# SCH-2-Main_Controls.net
KiCad netlist of a schematic drawn in Altium Designer
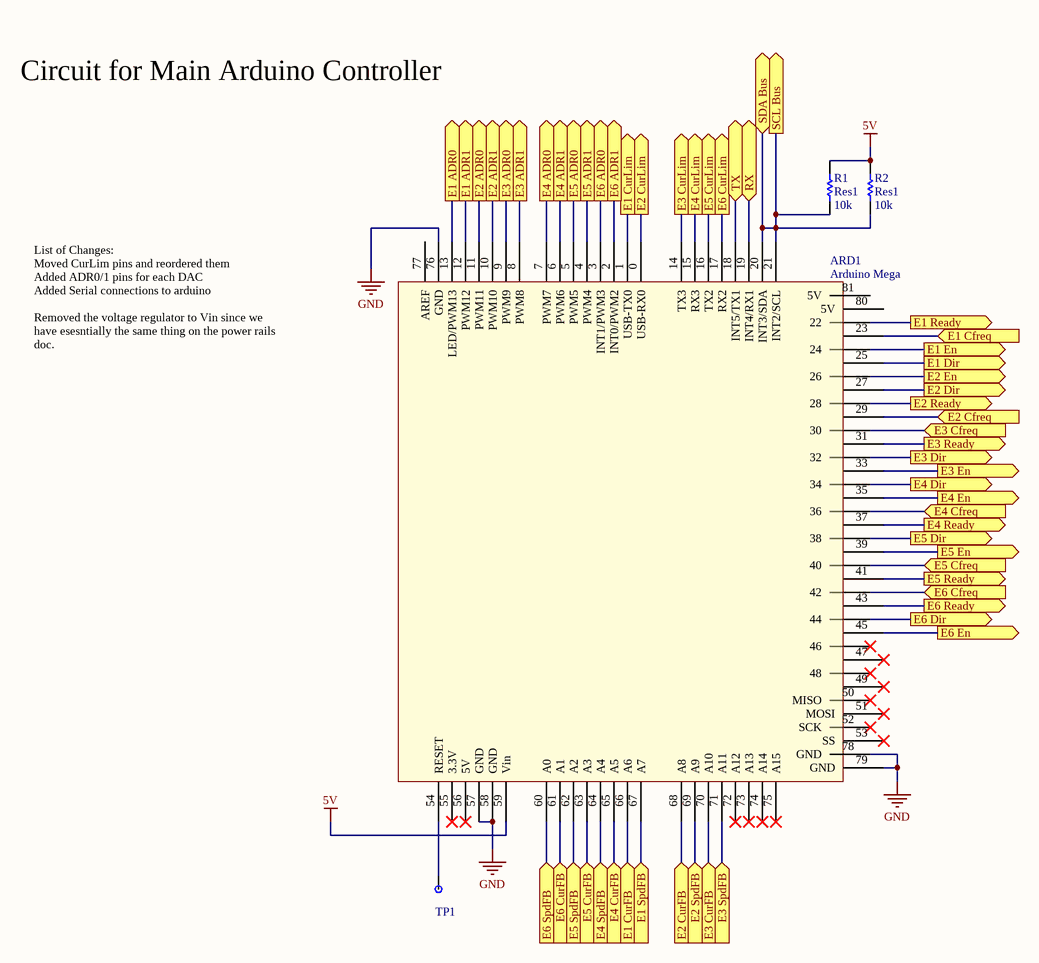
[diagram p0: SCH-2-Main Controls.SchDoc]

(export (version "E")
  (design (tool "Eeschema 10.0.6"))
  (components
    (comp (ref "ARD1")
      (value "Arduino Mega")
      (footprint "Arduino Mega")
      (libsource (lib "RSX_Schematics") (part "Arduino Mega"))
    )
    (comp (ref "R1")
      (value "Res1")
      (footprint "RESC1608X06N_0603")
      (description "Resistor")
      (fields (field (name "ALTIUM_VALUE") "10k") (field (name "PUBLISHER") "Altium Limited"))
      (libsource (lib "RSX_Resistors") (part "Res1"))
    )
    (comp (ref "R2")
      (value "Res1")
      (footprint "RESC1608X06N_0603")
      (description "Resistor")
      (fields (field (name "ALTIUM_VALUE") "10k") (field (name "PUBLISHER") "Altium Limited"))
      (libsource (lib "RSX_Resistors") (part "Res1"))
    )
    (comp (ref "TP1")
      (value "TestPt")
      (footprint "50_MIL_PAD")
      (libsource (lib "RSX_Test_Points") (part "TestPt"))
    )
  )
  (nets
    (net (code "1") (name "/E1 ADR0") (class "Default")
      (node (ref "ARD1") (pin "13") (pinfunction "LED/PWM13_13") (pintype "passive"))
    )
    (net (code "2") (name "/E1 ADR1") (class "Default")
      (node (ref "ARD1") (pin "12") (pinfunction "PWM12_12") (pintype "passive"))
    )
    (net (code "3") (name "/E1 Cfreq") (class "Default")
      (node (ref "ARD1") (pin "23") (pinfunction "23_23") (pintype "passive"))
    )
    (net (code "4") (name "/E1 CurFB") (class "Default")
      (node (ref "ARD1") (pin "66") (pinfunction "A6_66") (pintype "passive"))
    )
    (net (code "5") (name "/E1 CurLim") (class "Default")
      (node (ref "ARD1") (pin "1") (pinfunction "USB-TX0_1") (pintype "passive"))
    )
    (net (code "6") (name "/E1 Dir") (class "Default")
      (node (ref "ARD1") (pin "25") (pinfunction "25_25") (pintype "passive"))
    )
    (net (code "7") (name "/E1 En") (class "Default")
      (node (ref "ARD1") (pin "24") (pinfunction "24_24") (pintype "passive"))
    )
    (net (code "8") (name "/E1 Ready") (class "Default")
      (node (ref "ARD1") (pin "22") (pinfunction "22_22") (pintype "passive"))
    )
    (net (code "9") (name "/E1 SpdFB") (class "Default")
      (node (ref "ARD1") (pin "67") (pinfunction "A7_67") (pintype "passive"))
    )
    (net (code "10") (name "/E2 ADR0") (class "Default")
      (node (ref "ARD1") (pin "11") (pinfunction "PWM11_11") (pintype "passive"))
    )
    (net (code "11") (name "/E2 ADR1") (class "Default")
      (node (ref "ARD1") (pin "10") (pinfunction "PWM10_10") (pintype "passive"))
    )
    (net (code "12") (name "/E2 Cfreq") (class "Default")
      (node (ref "ARD1") (pin "29") (pinfunction "29_29") (pintype "passive"))
    )
    (net (code "13") (name "/E2 CurFB") (class "Default")
      (node (ref "ARD1") (pin "68") (pinfunction "A8_68") (pintype "passive"))
    )
    (net (code "14") (name "/E2 CurLim") (class "Default")
      (node (ref "ARD1") (pin "0") (pinfunction "USB-RX0_0") (pintype "passive"))
    )
    (net (code "15") (name "/E2 Dir") (class "Default")
      (node (ref "ARD1") (pin "27") (pinfunction "27_27") (pintype "passive"))
    )
    (net (code "16") (name "/E2 En") (class "Default")
      (node (ref "ARD1") (pin "26") (pinfunction "26_26") (pintype "passive"))
    )
    (net (code "17") (name "/E2 Ready") (class "Default")
      (node (ref "ARD1") (pin "28") (pinfunction "28_28") (pintype "passive"))
    )
    (net (code "18") (name "/E2 SpdFB") (class "Default")
      (node (ref "ARD1") (pin "69") (pinfunction "A9_69") (pintype "passive"))
    )
    (net (code "19") (name "/E3 ADR0") (class "Default")
      (node (ref "ARD1") (pin "9") (pinfunction "PWM9_9") (pintype "passive"))
    )
    (net (code "20") (name "/E3 ADR1") (class "Default")
      (node (ref "ARD1") (pin "8") (pinfunction "PWM8_8") (pintype "passive"))
    )
    (net (code "21") (name "/E3 Cfreq") (class "Default")
      (node (ref "ARD1") (pin "30") (pinfunction "30_30") (pintype "passive"))
    )
    (net (code "22") (name "/E3 CurFB") (class "Default")
      (node (ref "ARD1") (pin "70") (pinfunction "A10_70") (pintype "passive"))
    )
    (net (code "23") (name "/E3 CurLim") (class "Default")
      (node (ref "ARD1") (pin "14") (pinfunction "TX3_14") (pintype "passive"))
    )
    (net (code "24") (name "/E3 Dir") (class "Default")
      (node (ref "ARD1") (pin "32") (pinfunction "32_32") (pintype "passive"))
    )
    (net (code "25") (name "/E3 En") (class "Default")
      (node (ref "ARD1") (pin "33") (pinfunction "33_33") (pintype "passive"))
    )
    (net (code "26") (name "/E3 Ready") (class "Default")
      (node (ref "ARD1") (pin "31") (pinfunction "31_31") (pintype "passive"))
    )
    (net (code "27") (name "/E3 SpdFB") (class "Default")
      (node (ref "ARD1") (pin "71") (pinfunction "A11_71") (pintype "passive"))
    )
    (net (code "28") (name "/E4 ADR0") (class "Default")
      (node (ref "ARD1") (pin "7") (pinfunction "PWM7_7") (pintype "passive"))
    )
    (net (code "29") (name "/E4 ADR1") (class "Default")
      (node (ref "ARD1") (pin "6") (pinfunction "PWM6_6") (pintype "passive"))
    )
    (net (code "30") (name "/E4 Cfreq") (class "Default")
      (node (ref "ARD1") (pin "36") (pinfunction "36_36") (pintype "passive"))
    )
    (net (code "31") (name "/E4 CurFB") (class "Default")
      (node (ref "ARD1") (pin "65") (pinfunction "A5_65") (pintype "passive"))
    )
    (net (code "32") (name "/E4 CurLim") (class "Default")
      (node (ref "ARD1") (pin "15") (pinfunction "RX3_15") (pintype "passive"))
    )
    (net (code "33") (name "/E4 Dir") (class "Default")
      (node (ref "ARD1") (pin "34") (pinfunction "34_34") (pintype "passive"))
    )
    (net (code "34") (name "/E4 En") (class "Default")
      (node (ref "ARD1") (pin "35") (pinfunction "35_35") (pintype "passive"))
    )
    (net (code "35") (name "/E4 Ready") (class "Default")
      (node (ref "ARD1") (pin "37") (pinfunction "37_37") (pintype "passive"))
    )
    (net (code "36") (name "/E4 SpdFB") (class "Default")
      (node (ref "ARD1") (pin "64") (pinfunction "A4_64") (pintype "passive"))
    )
    (net (code "37") (name "/E5 ADR0") (class "Default")
      (node (ref "ARD1") (pin "5") (pinfunction "PWM5_5") (pintype "passive"))
    )
    (net (code "38") (name "/E5 ADR1") (class "Default")
      (node (ref "ARD1") (pin "4") (pinfunction "PWM4_4") (pintype "passive"))
    )
    (net (code "39") (name "/E5 Cfreq") (class "Default")
      (node (ref "ARD1") (pin "40") (pinfunction "40_40") (pintype "passive"))
    )
    (net (code "40") (name "/E5 CurFB") (class "Default")
      (node (ref "ARD1") (pin "63") (pinfunction "A3_63") (pintype "passive"))
    )
    (net (code "41") (name "/E5 CurLim") (class "Default")
      (node (ref "ARD1") (pin "16") (pinfunction "TX2_16") (pintype "passive"))
    )
    (net (code "42") (name "/E5 Dir") (class "Default")
      (node (ref "ARD1") (pin "38") (pinfunction "38_38") (pintype "passive"))
    )
    (net (code "43") (name "/E5 En") (class "Default")
      (node (ref "ARD1") (pin "39") (pinfunction "39_39") (pintype "passive"))
    )
    (net (code "44") (name "/E5 Ready") (class "Default")
      (node (ref "ARD1") (pin "41") (pinfunction "41_41") (pintype "passive"))
    )
    (net (code "45") (name "/E5 SpdFB") (class "Default")
      (node (ref "ARD1") (pin "62") (pinfunction "A2_62") (pintype "passive"))
    )
    (net (code "46") (name "/E6 ADR0") (class "Default")
      (node (ref "ARD1") (pin "3") (pinfunction "INT1/PWM3_3") (pintype "passive"))
    )
    (net (code "47") (name "/E6 ADR1") (class "Default")
      (node (ref "ARD1") (pin "2") (pinfunction "INT0/PWM2_2") (pintype "passive"))
    )
    (net (code "48") (name "/E6 Cfreq") (class "Default")
      (node (ref "ARD1") (pin "42") (pinfunction "42_42") (pintype "passive"))
    )
    (net (code "49") (name "/E6 CurFB") (class "Default")
      (node (ref "ARD1") (pin "61") (pinfunction "A1_61") (pintype "passive"))
    )
    (net (code "50") (name "/E6 CurLim") (class "Default")
      (node (ref "ARD1") (pin "17") (pinfunction "RX2_17") (pintype "passive"))
    )
    (net (code "51") (name "/E6 Dir") (class "Default")
      (node (ref "ARD1") (pin "44") (pinfunction "44_44") (pintype "passive"))
    )
    (net (code "52") (name "/E6 En") (class "Default")
      (node (ref "ARD1") (pin "45") (pinfunction "45_45") (pintype "passive"))
    )
    (net (code "53") (name "/E6 Ready") (class "Default")
      (node (ref "ARD1") (pin "43") (pinfunction "43_43") (pintype "passive"))
    )
    (net (code "54") (name "/E6 SpdFB") (class "Default")
      (node (ref "ARD1") (pin "60") (pinfunction "A0_60") (pintype "passive"))
    )
    (net (code "55") (name "/RX") (class "Default")
      (node (ref "ARD1") (pin "19") (pinfunction "INT4/RX1_19") (pintype "passive"))
    )
    (net (code "56") (name "/SCL Bus") (class "Default")
      (node (ref "ARD1") (pin "20") (pinfunction "INT3/SDA_20") (pintype "passive"))
      (node (ref "ARD1") (pin "21") (pinfunction "INT2/SCL_21") (pintype "passive"))
      (node (ref "R1") (pin "1") (pinfunction "1_1") (pintype "passive"))
      (node (ref "R2") (pin "1") (pinfunction "1_1") (pintype "passive"))
    )
    (net (code "57") (name "/TX") (class "Default")
      (node (ref "ARD1") (pin "18") (pinfunction "INT5/TX1_18") (pintype "passive"))
    )
    (net (code "58") (name "5V") (class "Default")
      (node (ref "ARD1") (pin "59") (pinfunction "Vin_59") (pintype "passive"))
      (node (ref "R1") (pin "2") (pinfunction "2_2") (pintype "passive"))
      (node (ref "R2") (pin "2") (pinfunction "2_2") (pintype "passive"))
    )
    (net (code "59") (name "GND") (class "Default")
      (node (ref "ARD1") (pin "57") (pinfunction "GND_57") (pintype "passive"))
      (node (ref "ARD1") (pin "58") (pinfunction "GND_58") (pintype "passive"))
      (node (ref "ARD1") (pin "76") (pinfunction "GND_76") (pintype "passive"))
      (node (ref "ARD1") (pin "78") (pinfunction "GND_78") (pintype "passive"))
      (node (ref "ARD1") (pin "79") (pinfunction "GND_79") (pintype "passive"))
    )
    (net (code "60") (name "Net-(ARD1-RESET)") (class "Default")
      (node (ref "ARD1") (pin "54") (pinfunction "RESET_54") (pintype "passive"))
      (node (ref "TP1") (pin "1") (pinfunction "1_1") (pintype "passive"))
    )
    (net (code "61") (name "unconnected-(ARD1-3.3V-Pad55)") (class "Default")
      (node (ref "ARD1") (pin "55") (pinfunction "3.3V_55") (pintype "passive+no_connect"))
    )
    (net (code "62") (name "unconnected-(ARD1-5V-Pad56)") (class "Default")
      (node (ref "ARD1") (pin "56") (pinfunction "5V_56") (pintype "passive+no_connect"))
    )
    (net (code "63") (name "unconnected-(ARD1-5V-Pad80)") (class "Default")
      (node (ref "ARD1") (pin "80") (pinfunction "5V_80") (pintype "passive"))
    )
    (net (code "64") (name "unconnected-(ARD1-5V-Pad81)") (class "Default")
      (node (ref "ARD1") (pin "81") (pinfunction "5V_81") (pintype "passive"))
    )
    (net (code "65") (name "unconnected-(ARD1-A12-Pad72)") (class "Default")
      (node (ref "ARD1") (pin "72") (pinfunction "A12_72") (pintype "passive+no_connect"))
    )
    (net (code "66") (name "unconnected-(ARD1-A13-Pad73)") (class "Default")
      (node (ref "ARD1") (pin "73") (pinfunction "A13_73") (pintype "passive+no_connect"))
    )
    (net (code "67") (name "unconnected-(ARD1-A14-Pad74)") (class "Default")
      (node (ref "ARD1") (pin "74") (pinfunction "A14_74") (pintype "passive+no_connect"))
    )
    (net (code "68") (name "unconnected-(ARD1-A15-Pad75)") (class "Default")
      (node (ref "ARD1") (pin "75") (pinfunction "A15_75") (pintype "passive+no_connect"))
    )
    (net (code "69") (name "unconnected-(ARD1-AREF-Pad77)") (class "Default")
      (node (ref "ARD1") (pin "77") (pinfunction "AREF_77") (pintype "passive"))
    )
    (net (code "70") (name "unconnected-(ARD1-MISO-Pad50)") (class "Default")
      (node (ref "ARD1") (pin "50") (pinfunction "MISO_50") (pintype "passive+no_connect"))
    )
    (net (code "71") (name "unconnected-(ARD1-MOSI-Pad51)") (class "Default")
      (node (ref "ARD1") (pin "51") (pinfunction "MOSI_51") (pintype "passive+no_connect"))
    )
    (net (code "72") (name "unconnected-(ARD1-Pad46)") (class "Default")
      (node (ref "ARD1") (pin "46") (pinfunction "46_46") (pintype "passive+no_connect"))
    )
    (net (code "73") (name "unconnected-(ARD1-Pad47)") (class "Default")
      (node (ref "ARD1") (pin "47") (pinfunction "47_47") (pintype "passive+no_connect"))
    )
    (net (code "74") (name "unconnected-(ARD1-Pad48)") (class "Default")
      (node (ref "ARD1") (pin "48") (pinfunction "48_48") (pintype "passive+no_connect"))
    )
    (net (code "75") (name "unconnected-(ARD1-Pad49)") (class "Default")
      (node (ref "ARD1") (pin "49") (pinfunction "49_49") (pintype "passive+no_connect"))
    )
    (net (code "76") (name "unconnected-(ARD1-SCK-Pad52)") (class "Default")
      (node (ref "ARD1") (pin "52") (pinfunction "SCK_52") (pintype "passive+no_connect"))
    )
    (net (code "77") (name "unconnected-(ARD1-SS-Pad53)") (class "Default")
      (node (ref "ARD1") (pin "53") (pinfunction "SS_53") (pintype "passive+no_connect"))
    )
  )
)
